# rev02_10.net
KiCad netlist of a schematic drawn in Altium Designer
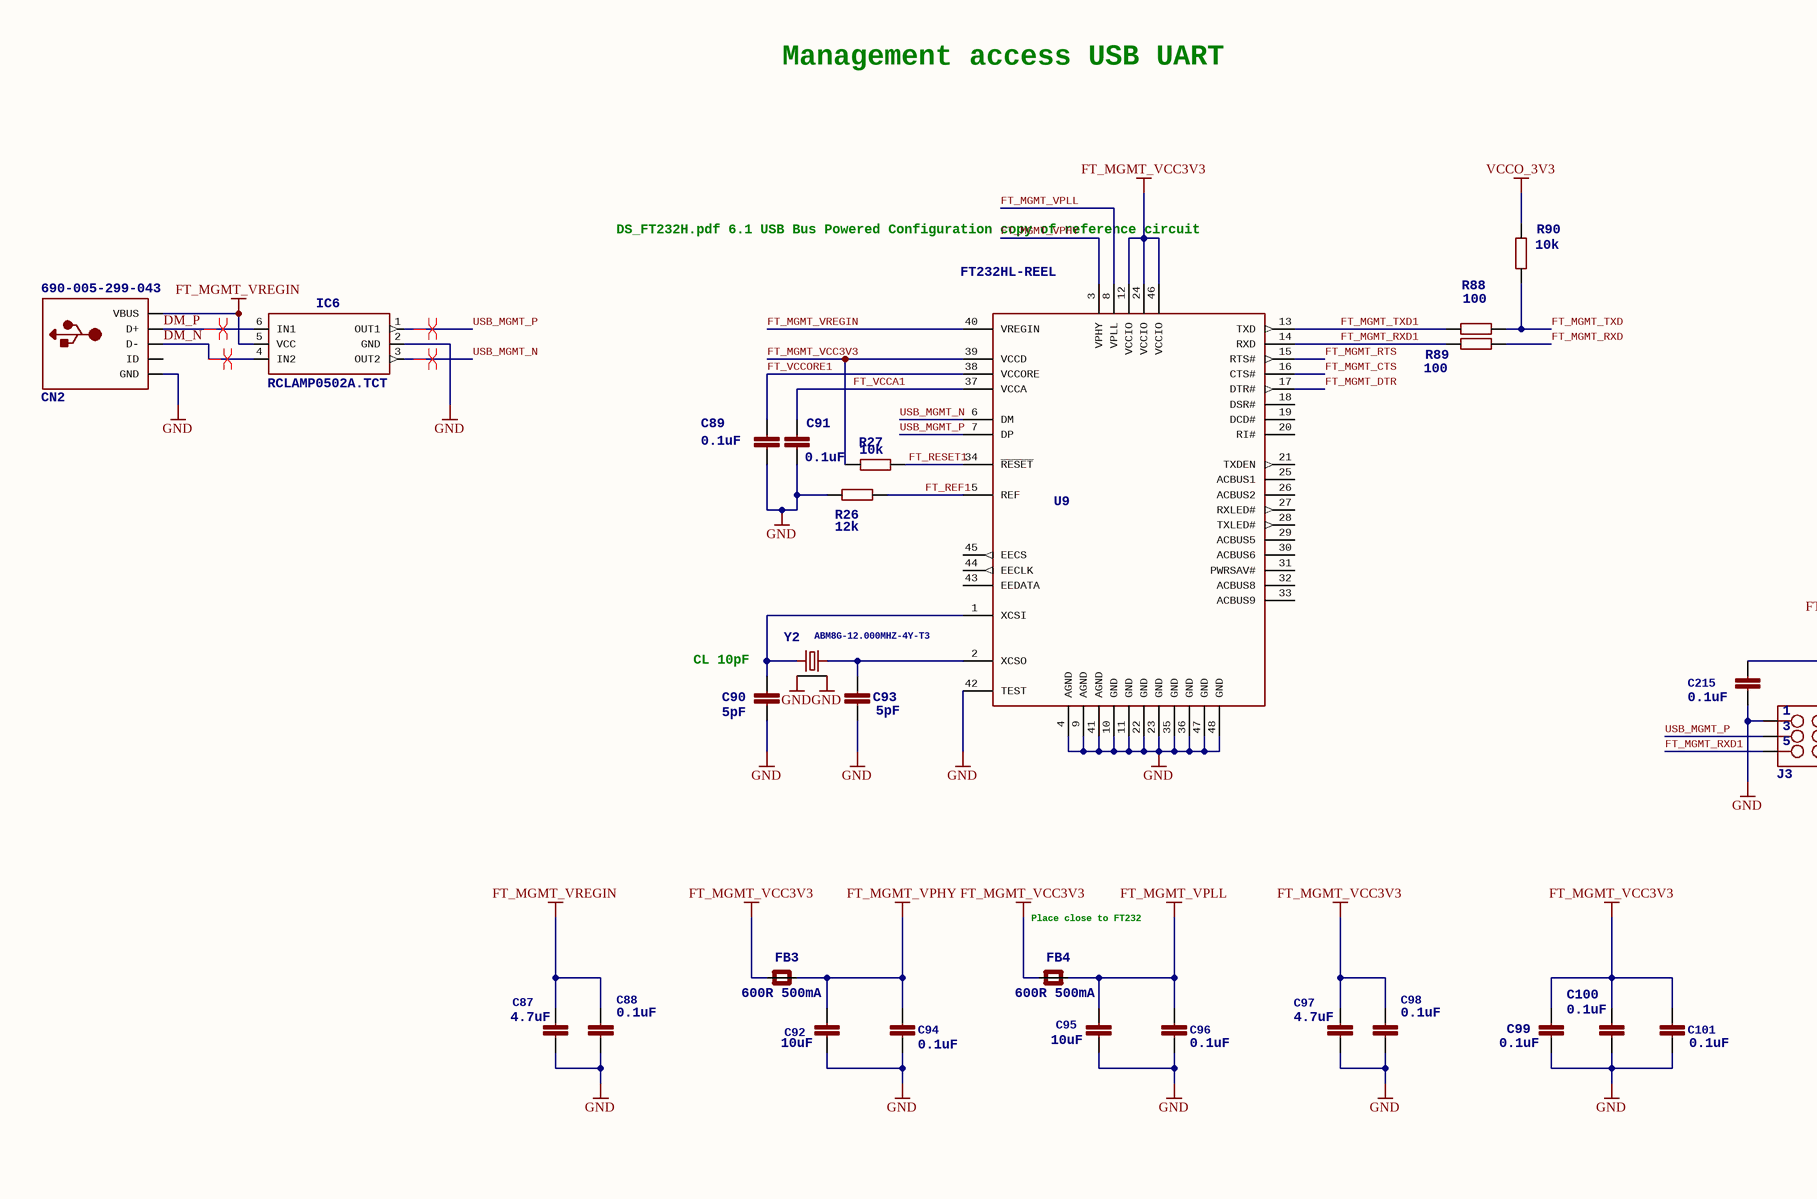
[diagram p0: rev02_10.SchDoc, left]
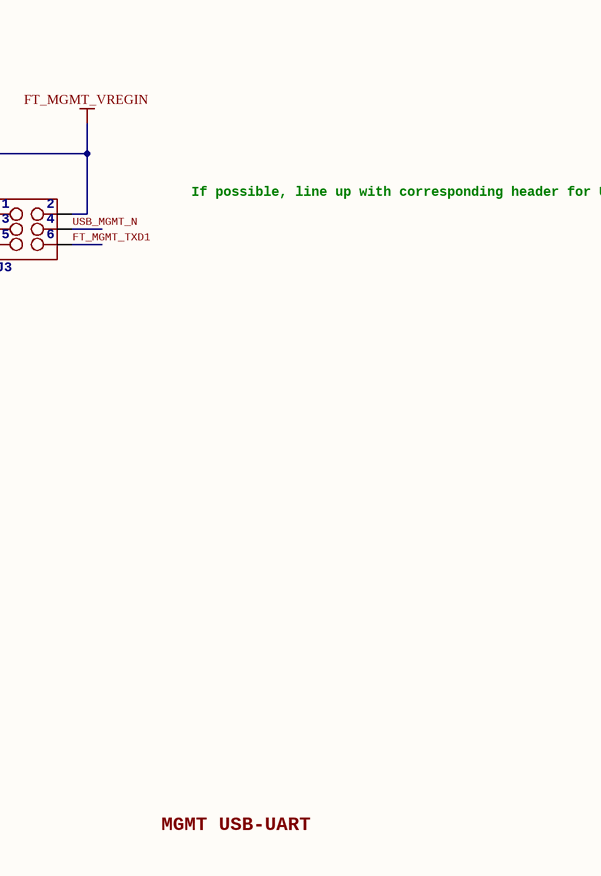
[diagram p1: rev02_10.SchDoc, right]

(export (version "E")
  (design (tool "Eeschema 10.0.6"))
  (components
    (comp (ref "C87")
      (value "4.7uF")
      (footprint "C_0805")
      (description "0805 CAPACITOR")
      (fields (field (name "Comment") "GRM21BR71A475KA73L"))
      (libsource (lib "resistor") (part "C-EUC0603"))
    )
    (comp (ref "C88")
      (value "0.1uF")
      (footprint "C_0402")
      (description "0402 CAPACITOR")
      (libsource (lib "resistor") (part "C-EUC0402"))
    )
    (comp (ref "C89")
      (value "0.1uF")
      (footprint "C_0402")
      (description "0402 CAPACITOR")
      (libsource (lib "resistor") (part "C-EUC0402"))
    )
    (comp (ref "C90")
      (value "5pF")
      (footprint "C_0402")
      (description "0402 CAPACITOR")
      (libsource (lib "") (part "C-EUC0402_1"))
    )
    (comp (ref "C91")
      (value "0.1uF")
      (footprint "C_0402")
      (description "0402 CAPACITOR")
      (fields (field (name ">NAME") "C91"))
      (libsource (lib "resistor") (part "C-EUC0402"))
    )
    (comp (ref "C92")
      (value "10uF")
      (footprint "C_0805")
      (description "0805 CAPACITOR")
      (libsource (lib "resistor") (part "C-EUC0805"))
    )
    (comp (ref "C93")
      (value "5pF")
      (footprint "C_0402")
      (description "0402 CAPACITOR")
      (libsource (lib "") (part "C-EUC0402_1"))
    )
    (comp (ref "C94")
      (value "0.1uF")
      (footprint "C_0402")
      (description "0402 CAPACITOR")
      (libsource (lib "resistor") (part "C-EUC0402"))
    )
    (comp (ref "C95")
      (value "10uF")
      (footprint "C_0805")
      (description "0805 CAPACITOR")
      (libsource (lib "resistor") (part "C-EUC0805"))
    )
    (comp (ref "C96")
      (value "0.1uF")
      (footprint "C_0402")
      (description "0402 CAPACITOR")
      (libsource (lib "resistor") (part "C-EUC0402"))
    )
    (comp (ref "C97")
      (value "4.7uF")
      (footprint "C_0805")
      (description "0805 CAPACITOR")
      (fields (field (name "Comment") "GRM21BR71A475KA73L"))
      (libsource (lib "resistor") (part "C-EUC0603"))
    )
    (comp (ref "C98")
      (value "0.1uF")
      (footprint "C_0402")
      (description "0402 CAPACITOR")
      (libsource (lib "resistor") (part "C-EUC0402"))
    )
    (comp (ref "C99")
      (value "0.1uF")
      (footprint "C_0402")
      (description "0402 CAPACITOR")
      (libsource (lib "resistor") (part "C-EUC0402"))
    )
    (comp (ref "C100")
      (value "0.1uF")
      (footprint "C_0402")
      (description "0402 CAPACITOR")
      (libsource (lib "resistor") (part "C-EUC0402"))
    )
    (comp (ref "C101")
      (value "0.1uF")
      (footprint "C_0402")
      (description "0402 CAPACITOR")
      (libsource (lib "resistor") (part "C-EUC0402"))
    )
    (comp (ref "C215")
      (value "0.1uF")
      (footprint "C_0402")
      (description "0402 CAPACITOR")
      (libsource (lib "resistor") (part "C-EUC0402"))
    )
    (comp (ref "CN2")
      (value "690-005-299-043")
      (footprint "USB-MINIB")
      (description "mini USB type B Connector")
      (libsource (lib "adafruit") (part "USBMINIB"))
    )
    (comp (ref "FB3")
      (value "FBMH1608HL601-T")
      (footprint "L_0603")
      (description "Ferrite Bead 600 Ohm 500mA")
      (fields (field (name ">NAME") "FB3") (field (name ">VALUE") "600R 500mA"))
      (libsource (lib "microbuilder") (part "FERRITE_0603MP"))
    )
    (comp (ref "FB4")
      (value "FBMH1608HL601-T")
      (footprint "L_0603")
      (description "Ferrite Bead 600 Ohm 500mA")
      (fields (field (name ">NAME") "FB4") (field (name ">VALUE") "600R 500mA"))
      (libsource (lib "microbuilder") (part "FERRITE_0603MP"))
    )
    (comp (ref "IC6")
      (value "RCLAMP0502A.TCT")
      (footprint "RCLAMP0502A")
      (description "USB protective diodes")
      (fields (field (name "MFR") "SEMTECH") (field (name "MPN") "RCLAMP0502A") (field (name ">NAME") "IC6"))
      (libsource (lib "UsedComponents") (part "RCLAMP0502ASC-89"))
    )
    (comp (ref "J3")
      (value "M03X2NO_SILK")
      (footprint "PLD-6")
      (description "2x3 .1\" header")
      (fields
        (field (name "1") "1")
        (field (name "2") "2")
        (field (name "3") "3")
        (field (name "4") "4")
        (field (name "5") "5")
        (field (name "6") "6")
      )
      (libsource (lib "SparkFun-Connectors") (part "M03X2NO_SILK"))
    )
    (comp (ref "R26")
      (value "12k")
      (footprint "R_0402")
      (description "0402 Resistor 1%")
      (libsource (lib "resistor") (part "R-EU_R0402"))
    )
    (comp (ref "R27")
      (value "10k")
      (footprint "R_0402")
      (description "0402 Resistor 5%")
      (fields (field (name "TOLERANCE") "5%") (field (name ">NAME") "R27"))
      (libsource (lib "resistor") (part "R-EU_R0402"))
    )
    (comp (ref "R88")
      (value "100")
      (footprint "R_0402")
      (description "0402 Resistor 5%")
      (libsource (lib "resistor") (part "R-EU_R0402"))
    )
    (comp (ref "R89")
      (value "100")
      (footprint "R_0402")
      (description "0402 Resistor 5%")
      (libsource (lib "resistor") (part "R-EU_R0402"))
    )
    (comp (ref "R90")
      (value "10k")
      (footprint "R_0402")
      (description "0402 Resistor 5%")
      (libsource (lib "resistor") (part "R-EU_R0402"))
    )
    (comp (ref "U9")
      (value "FT232HL-REEL")
      (footprint "LQFP-48")
      (description "INTERFACE, USB - UART/FIFO")
      (fields (field (name ">NAME") "U9"))
      (libsource (lib "Alpha-IC") (part "FT232H_SERIAL"))
    )
    (comp (ref "Y2")
      (value "ABM8G-12.000MHZ-4Y-T3")
      (footprint "CRYSTAL_3.2X2.5")
      (description "Crystal 12MHz")
      (libsource (lib "rev02_1") (part "CRYSTALTHIN"))
    )
  )
  (nets
    (net (code "1") (name "/DM_N") (class "Default")
      (node (ref "CN2") (pin "D-") (pinfunction "D-_D-") (pintype "passive"))
      (node (ref "IC6") (pin "4") (pinfunction "IN2_4") (pintype "passive"))
    )
    (net (code "2") (name "/DM_P") (class "Default")
      (node (ref "CN2") (pin "D+") (pinfunction "D+_D+") (pintype "passive"))
      (node (ref "IC6") (pin "6") (pinfunction "IN1_6") (pintype "passive"))
    )
    (net (code "3") (name "/FT_MGMT_CTS") (class "Default")
      (node (ref "U9") (pin "16") (pinfunction "CTS#_16") (pintype "passive"))
    )
    (net (code "4") (name "/FT_MGMT_DTR") (class "Default")
      (node (ref "U9") (pin "17") (pinfunction "DTR#_17") (pintype "output"))
    )
    (net (code "5") (name "/FT_MGMT_RTS") (class "Default")
      (node (ref "U9") (pin "15") (pinfunction "RTS#_15") (pintype "output"))
    )
    (net (code "6") (name "/FT_MGMT_RXD") (class "Default")
      (node (ref "R89") (pin "1") (pinfunction "1_1") (pintype "passive"))
    )
    (net (code "7") (name "/FT_MGMT_RXD1") (class "Default")
      (node (ref "J3") (pin "5") (pinfunction "5_5") (pintype "passive"))
      (node (ref "R89") (pin "2") (pinfunction "2_2") (pintype "passive"))
      (node (ref "U9") (pin "14") (pinfunction "RXD_14") (pintype "passive"))
    )
    (net (code "8") (name "/FT_MGMT_TXD") (class "Default")
      (node (ref "R88") (pin "1") (pinfunction "1_1") (pintype "passive"))
      (node (ref "R90") (pin "2") (pinfunction "2_2") (pintype "passive"))
    )
    (net (code "9") (name "/FT_MGMT_TXD1") (class "Default")
      (node (ref "J3") (pin "6") (pinfunction "6_6") (pintype "passive"))
      (node (ref "R88") (pin "2") (pinfunction "2_2") (pintype "passive"))
      (node (ref "U9") (pin "13") (pinfunction "TXD_13") (pintype "output"))
    )
    (net (code "10") (name "/FT_REF1") (class "Default")
      (node (ref "R26") (pin "1") (pinfunction "1_1") (pintype "passive"))
      (node (ref "U9") (pin "5") (pinfunction "REF_5") (pintype "passive"))
    )
    (net (code "11") (name "/FT_RESET1") (class "Default")
      (node (ref "R27") (pin "1") (pinfunction "1_1") (pintype "passive"))
      (node (ref "U9") (pin "34") (pinfunction "~{RESET}_34") (pintype "passive"))
    )
    (net (code "12") (name "/FT_VCCA1") (class "Default")
      (node (ref "C91") (pin "1") (pinfunction "1_1") (pintype "passive"))
      (node (ref "U9") (pin "37") (pinfunction "VCCA_37") (pintype "power_in"))
    )
    (net (code "13") (name "/FT_VCCORE1") (class "Default")
      (node (ref "C89") (pin "1") (pinfunction "1_1") (pintype "passive"))
      (node (ref "U9") (pin "38") (pinfunction "VCCORE_38") (pintype "power_in"))
    )
    (net (code "14") (name "/USB_MGMT_N") (class "Default")
      (node (ref "IC6") (pin "3") (pinfunction "OUT2_3") (pintype "output"))
      (node (ref "J3") (pin "4") (pinfunction "4_4") (pintype "passive"))
      (node (ref "U9") (pin "6") (pinfunction "DM_6") (pintype "passive"))
    )
    (net (code "15") (name "/USB_MGMT_P") (class "Default")
      (node (ref "IC6") (pin "1") (pinfunction "OUT1_1") (pintype "output"))
      (node (ref "J3") (pin "3") (pinfunction "3_3") (pintype "passive"))
      (node (ref "U9") (pin "7") (pinfunction "DP_7") (pintype "passive"))
    )
    (net (code "16") (name "FT_MGMT_VCC3V3") (class "Default")
      (node (ref "C100") (pin "1") (pinfunction "1_1") (pintype "passive"))
      (node (ref "C101") (pin "1") (pinfunction "1_1") (pintype "passive"))
      (node (ref "C97") (pin "1") (pinfunction "1_1") (pintype "passive"))
      (node (ref "C98") (pin "1") (pinfunction "1_1") (pintype "passive"))
      (node (ref "C99") (pin "1") (pinfunction "1_1") (pintype "passive"))
      (node (ref "FB3") (pin "1") (pinfunction "P$1_1") (pintype "passive"))
      (node (ref "FB4") (pin "1") (pinfunction "P$1_1") (pintype "passive"))
      (node (ref "R27") (pin "2") (pinfunction "2_2") (pintype "passive"))
      (node (ref "U9") (pin "12") (pinfunction "VCCIO_12") (pintype "power_in"))
      (node (ref "U9") (pin "24") (pinfunction "VCCIO_24") (pintype "power_in"))
      (node (ref "U9") (pin "39") (pinfunction "VCCD_39") (pintype "power_in"))
      (node (ref "U9") (pin "46") (pinfunction "VCCIO_46") (pintype "power_in"))
    )
    (net (code "17") (name "FT_MGMT_VPHY") (class "Default")
      (node (ref "C92") (pin "1") (pinfunction "1_1") (pintype "passive"))
      (node (ref "C94") (pin "1") (pinfunction "1_1") (pintype "passive"))
      (node (ref "FB3") (pin "2") (pinfunction "P$2_2") (pintype "passive"))
      (node (ref "U9") (pin "3") (pinfunction "VPHY_3") (pintype "passive"))
    )
    (net (code "18") (name "FT_MGMT_VPLL") (class "Default")
      (node (ref "C95") (pin "1") (pinfunction "1_1") (pintype "passive"))
      (node (ref "C96") (pin "1") (pinfunction "1_1") (pintype "passive"))
      (node (ref "FB4") (pin "2") (pinfunction "P$2_2") (pintype "passive"))
      (node (ref "U9") (pin "8") (pinfunction "VPLL_8") (pintype "passive"))
    )
    (net (code "19") (name "FT_MGMT_VREGIN") (class "Default")
      (node (ref "C215") (pin "1") (pinfunction "1_1") (pintype "passive"))
      (node (ref "C87") (pin "1") (pinfunction "1_1") (pintype "passive"))
      (node (ref "C88") (pin "1") (pinfunction "1_1") (pintype "passive"))
      (node (ref "CN2") (pin "VBUS") (pinfunction "VBUS_VBUS") (pintype "power_in"))
      (node (ref "IC6") (pin "5") (pinfunction "VCC_5") (pintype "power_in"))
      (node (ref "J3") (pin "2") (pinfunction "2_2") (pintype "passive"))
      (node (ref "U9") (pin "40") (pinfunction "VREGIN_40") (pintype "power_in"))
    )
    (net (code "20") (name "GND") (class "Default")
      (node (ref "C100") (pin "2") (pinfunction "2_2") (pintype "passive"))
      (node (ref "C101") (pin "2") (pinfunction "2_2") (pintype "passive"))
      (node (ref "C215") (pin "2") (pinfunction "2_2") (pintype "passive"))
      (node (ref "C87") (pin "2") (pinfunction "2_2") (pintype "passive"))
      (node (ref "C88") (pin "2") (pinfunction "2_2") (pintype "passive"))
      (node (ref "C89") (pin "2") (pinfunction "2_2") (pintype "passive"))
      (node (ref "C90") (pin "1") (pinfunction "1_1") (pintype "passive"))
      (node (ref "C91") (pin "2") (pinfunction "2_2") (pintype "passive"))
      (node (ref "C92") (pin "2") (pinfunction "2_2") (pintype "passive"))
      (node (ref "C93") (pin "1") (pinfunction "1_1") (pintype "passive"))
      (node (ref "C94") (pin "2") (pinfunction "2_2") (pintype "passive"))
      (node (ref "C95") (pin "2") (pinfunction "2_2") (pintype "passive"))
      (node (ref "C96") (pin "2") (pinfunction "2_2") (pintype "passive"))
      (node (ref "C97") (pin "2") (pinfunction "2_2") (pintype "passive"))
      (node (ref "C98") (pin "2") (pinfunction "2_2") (pintype "passive"))
      (node (ref "C99") (pin "2") (pinfunction "2_2") (pintype "passive"))
      (node (ref "CN2") (pin "GND") (pinfunction "GND_GND") (pintype "power_in"))
      (node (ref "IC6") (pin "2") (pinfunction "GND_2") (pintype "power_in"))
      (node (ref "J3") (pin "1") (pinfunction "1_1") (pintype "passive"))
      (node (ref "R26") (pin "2") (pinfunction "2_2") (pintype "passive"))
      (node (ref "U9") (pin "10") (pinfunction "GND_10") (pintype "power_in"))
      (node (ref "U9") (pin "11") (pinfunction "GND_11") (pintype "power_in"))
      (node (ref "U9") (pin "22") (pinfunction "GND_22") (pintype "power_in"))
      (node (ref "U9") (pin "23") (pinfunction "GND_23") (pintype "power_in"))
      (node (ref "U9") (pin "35") (pinfunction "GND_35") (pintype "power_in"))
      (node (ref "U9") (pin "36") (pinfunction "GND_36") (pintype "power_in"))
      (node (ref "U9") (pin "4") (pinfunction "AGND_4") (pintype "power_in"))
      (node (ref "U9") (pin "41") (pinfunction "AGND_41") (pintype "power_in"))
      (node (ref "U9") (pin "42") (pinfunction "TEST_42") (pintype "passive"))
      (node (ref "U9") (pin "47") (pinfunction "GND_47") (pintype "power_in"))
      (node (ref "U9") (pin "48") (pinfunction "GND_48") (pintype "power_in"))
      (node (ref "U9") (pin "9") (pinfunction "AGND_9") (pintype "power_in"))
      (node (ref "Y2") (pin "2") (pinfunction "2_2") (pintype "passive"))
      (node (ref "Y2") (pin "4") (pinfunction "4_4") (pintype "passive"))
    )
    (net (code "21") (name "Net-(U9-XCSI)") (class "Default")
      (node (ref "C90") (pin "2") (pinfunction "2_2") (pintype "passive"))
      (node (ref "U9") (pin "1") (pinfunction "XCSI_1") (pintype "passive"))
      (node (ref "Y2") (pin "3") (pinfunction "3_3") (pintype "passive"))
    )
    (net (code "22") (name "Net-(U9-XCSO)") (class "Default")
      (node (ref "C93") (pin "2") (pinfunction "2_2") (pintype "passive"))
      (node (ref "U9") (pin "2") (pinfunction "XCSO_2") (pintype "passive"))
      (node (ref "Y2") (pin "1") (pinfunction "1_1") (pintype "passive"))
    )
    (net (code "23") (name "VCCO_3V3") (class "Default")
      (node (ref "R90") (pin "1") (pinfunction "1_1") (pintype "passive"))
    )
    (net (code "24") (name "unconnected-(CN2-PadID)") (class "Default")
      (node (ref "CN2") (pin "ID") (pinfunction "ID_ID") (pintype "passive"))
    )
    (net (code "25") (name "unconnected-(U9-ACBUS1-Pad25)") (class "Default")
      (node (ref "U9") (pin "25") (pinfunction "ACBUS1_25") (pintype "passive"))
    )
    (net (code "26") (name "unconnected-(U9-ACBUS2-Pad26)") (class "Default")
      (node (ref "U9") (pin "26") (pinfunction "ACBUS2_26") (pintype "passive"))
    )
    (net (code "27") (name "unconnected-(U9-ACBUS5-Pad29)") (class "Default")
      (node (ref "U9") (pin "29") (pinfunction "ACBUS5_29") (pintype "passive"))
    )
    (net (code "28") (name "unconnected-(U9-ACBUS6-Pad30)") (class "Default")
      (node (ref "U9") (pin "30") (pinfunction "ACBUS6_30") (pintype "passive"))
    )
    (net (code "29") (name "unconnected-(U9-ACBUS8-Pad32)") (class "Default")
      (node (ref "U9") (pin "32") (pinfunction "ACBUS8_32") (pintype "passive"))
    )
    (net (code "30") (name "unconnected-(U9-ACBUS9-Pad33)") (class "Default")
      (node (ref "U9") (pin "33") (pinfunction "ACBUS9_33") (pintype "passive"))
    )
    (net (code "31") (name "unconnected-(U9-DCD#-Pad19)") (class "Default")
      (node (ref "U9") (pin "19") (pinfunction "DCD#_19") (pintype "passive"))
    )
    (net (code "32") (name "unconnected-(U9-DSR#-Pad18)") (class "Default")
      (node (ref "U9") (pin "18") (pinfunction "DSR#_18") (pintype "passive"))
    )
    (net (code "33") (name "unconnected-(U9-EECLK-Pad44)") (class "Default")
      (node (ref "U9") (pin "44") (pinfunction "EECLK_44") (pintype "output"))
    )
    (net (code "34") (name "unconnected-(U9-EECS-Pad45)") (class "Default")
      (node (ref "U9") (pin "45") (pinfunction "EECS_45") (pintype "output"))
    )
    (net (code "35") (name "unconnected-(U9-EEDATA-Pad43)") (class "Default")
      (node (ref "U9") (pin "43") (pinfunction "EEDATA_43") (pintype "passive"))
    )
    (net (code "36") (name "unconnected-(U9-PWRSAV#-Pad31)") (class "Default")
      (node (ref "U9") (pin "31") (pinfunction "PWRSAV#_31") (pintype "passive"))
    )
    (net (code "37") (name "unconnected-(U9-RI#-Pad20)") (class "Default")
      (node (ref "U9") (pin "20") (pinfunction "RI#_20") (pintype "passive"))
    )
    (net (code "38") (name "unconnected-(U9-RXLED#-Pad27)") (class "Default")
      (node (ref "U9") (pin "27") (pinfunction "RXLED#_27") (pintype "output"))
    )
    (net (code "39") (name "unconnected-(U9-TXDEN-Pad21)") (class "Default")
      (node (ref "U9") (pin "21") (pinfunction "TXDEN_21") (pintype "output"))
    )
    (net (code "40") (name "unconnected-(U9-TXLED#-Pad28)") (class "Default")
      (node (ref "U9") (pin "28") (pinfunction "TXLED#_28") (pintype "output"))
    )
  )
)
